# Schematic.net
KiCad netlist of a schematic drawn in Altium Designer
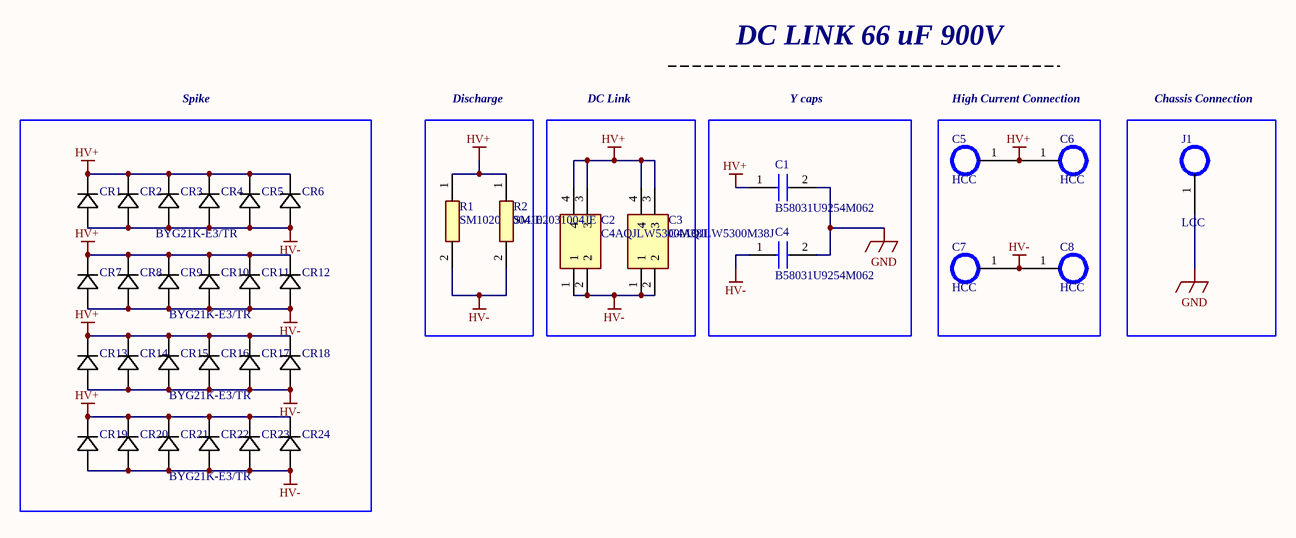
[diagram p0: Schematic.SchDoc]

(export (version "E")
  (design (tool "Eeschema 10.0.6"))
  (components
    (comp (ref "C1")
      (value "B58031U9254M062")
      (footprint "B58031U9254M062")
      (description "Capacitor")
      (fields (field (name "MOUSER PART NUMBER") "871-B58031U9254M062"))
      (libsource (lib "Schlib3") (part "B58031U9254M062"))
    )
    (comp (ref "C2")
      (value "C4AQJLW5300M38J")
      (footprint "PcbLib3:C4AQJLW5300M38J")
      (description "Capacitor")
      (fields (field (name "MOUSER PART NUMBER") "80-C4AQJLW5300M38J"))
      (libsource (lib "Schlib3") (part "C4AQJLW5300M38J"))
    )
    (comp (ref "C3")
      (value "C4AQJLW5300M38J")
      (footprint "PcbLib3:C4AQJLW5300M38J")
      (description "Capacitor")
      (fields (field (name "MOUSER PART NUMBER") "80-C4AQJLW5300M38J"))
      (libsource (lib "Schlib3") (part "C4AQJLW5300M38J"))
    )
    (comp (ref "C4")
      (value "B58031U9254M062")
      (footprint "B58031U9254M062")
      (description "Capacitor")
      (fields (field (name "MOUSER PART NUMBER") "871-B58031U9254M062"))
      (libsource (lib "Schlib3") (part "B58031U9254M062"))
    )
    (comp (ref "C5") (value "HCC") (footprint "6mm Pad") (libsource (lib "Schlib3") (part "HCC")))
    (comp (ref "C6") (value "HCC") (footprint "6mm Pad") (libsource (lib "Schlib3") (part "HCC")))
    (comp (ref "C7") (value "HCC") (footprint "6mm Pad") (libsource (lib "Schlib3") (part "HCC")))
    (comp (ref "C8") (value "HCC") (footprint "6mm Pad") (libsource (lib "Schlib3") (part "HCC")))
    (comp (ref "CR1")
      (value "BYG21K-E3/TR")
      (footprint "DO-214AC_VIS")
      (description "1.5A,800V,120nS FS AVALANCHE SMD")
      (fields (field (name "COPYRIGHT") "Copyright (C) 2025 Ultra Librarian. All rights reserved."))
      (libsource (lib "Schlib3") (part "BYG21K-E3TR"))
    )
    (comp (ref "CR2")
      (value "BYG21K-E3/TR")
      (footprint "DO-214AC_VIS")
      (description "1.5A,800V,120nS FS AVALANCHE SMD")
      (fields (field (name "COPYRIGHT") "Copyright (C) 2025 Ultra Librarian. All rights reserved."))
      (libsource (lib "Schlib3") (part "BYG21K-E3TR"))
    )
    (comp (ref "CR3")
      (value "BYG21K-E3/TR")
      (footprint "DO-214AC_VIS")
      (description "1.5A,800V,120nS FS AVALANCHE SMD")
      (fields (field (name "COPYRIGHT") "Copyright (C) 2025 Ultra Librarian. All rights reserved."))
      (libsource (lib "Schlib3") (part "BYG21K-E3TR"))
    )
    (comp (ref "CR4")
      (value "BYG21K-E3/TR")
      (footprint "DO-214AC_VIS")
      (description "1.5A,800V,120nS FS AVALANCHE SMD")
      (fields (field (name "COPYRIGHT") "Copyright (C) 2025 Ultra Librarian. All rights reserved."))
      (libsource (lib "Schlib3") (part "BYG21K-E3TR"))
    )
    (comp (ref "CR5")
      (value "BYG21K-E3/TR")
      (footprint "DO-214AC_VIS")
      (description "1.5A,800V,120nS FS AVALANCHE SMD")
      (fields (field (name "COPYRIGHT") "Copyright (C) 2025 Ultra Librarian. All rights reserved."))
      (libsource (lib "Schlib3") (part "BYG21K-E3TR"))
    )
    (comp (ref "CR6")
      (value "BYG21K-E3/TR")
      (footprint "DO-214AC_VIS")
      (description "1.5A,800V,120nS FS AVALANCHE SMD")
      (fields (field (name "COPYRIGHT") "Copyright (C) 2025 Ultra Librarian. All rights reserved."))
      (libsource (lib "Schlib3") (part "BYG21K-E3TR"))
    )
    (comp (ref "CR7")
      (value "BYG21K-E3/TR")
      (footprint "DO-214AC_VIS")
      (description "1.5A,800V,120nS FS AVALANCHE SMD")
      (fields (field (name "COPYRIGHT") "Copyright (C) 2025 Ultra Librarian. All rights reserved."))
      (libsource (lib "Schlib3") (part "BYG21K-E3TR"))
    )
    (comp (ref "CR8")
      (value "BYG21K-E3/TR")
      (footprint "DO-214AC_VIS")
      (description "1.5A,800V,120nS FS AVALANCHE SMD")
      (fields (field (name "COPYRIGHT") "Copyright (C) 2025 Ultra Librarian. All rights reserved."))
      (libsource (lib "Schlib3") (part "BYG21K-E3TR"))
    )
    (comp (ref "CR9")
      (value "BYG21K-E3/TR")
      (footprint "DO-214AC_VIS")
      (description "1.5A,800V,120nS FS AVALANCHE SMD")
      (fields (field (name "COPYRIGHT") "Copyright (C) 2025 Ultra Librarian. All rights reserved."))
      (libsource (lib "Schlib3") (part "BYG21K-E3TR"))
    )
    (comp (ref "CR10")
      (value "BYG21K-E3/TR")
      (footprint "DO-214AC_VIS")
      (description "1.5A,800V,120nS FS AVALANCHE SMD")
      (fields (field (name "COPYRIGHT") "Copyright (C) 2025 Ultra Librarian. All rights reserved."))
      (libsource (lib "Schlib3") (part "BYG21K-E3TR"))
    )
    (comp (ref "CR11")
      (value "BYG21K-E3/TR")
      (footprint "DO-214AC_VIS")
      (description "1.5A,800V,120nS FS AVALANCHE SMD")
      (fields (field (name "COPYRIGHT") "Copyright (C) 2025 Ultra Librarian. All rights reserved."))
      (libsource (lib "Schlib3") (part "BYG21K-E3TR"))
    )
    (comp (ref "CR12")
      (value "BYG21K-E3/TR")
      (footprint "DO-214AC_VIS")
      (description "1.5A,800V,120nS FS AVALANCHE SMD")
      (fields (field (name "COPYRIGHT") "Copyright (C) 2025 Ultra Librarian. All rights reserved."))
      (libsource (lib "Schlib3") (part "BYG21K-E3TR"))
    )
    (comp (ref "CR13")
      (value "BYG21K-E3/TR")
      (footprint "DO-214AC_VIS")
      (description "1.5A,800V,120nS FS AVALANCHE SMD")
      (fields (field (name "COPYRIGHT") "Copyright (C) 2025 Ultra Librarian. All rights reserved."))
      (libsource (lib "Schlib3") (part "BYG21K-E3TR"))
    )
    (comp (ref "CR14")
      (value "BYG21K-E3/TR")
      (footprint "DO-214AC_VIS")
      (description "1.5A,800V,120nS FS AVALANCHE SMD")
      (fields (field (name "COPYRIGHT") "Copyright (C) 2025 Ultra Librarian. All rights reserved."))
      (libsource (lib "Schlib3") (part "BYG21K-E3TR"))
    )
    (comp (ref "CR15")
      (value "BYG21K-E3/TR")
      (footprint "DO-214AC_VIS")
      (description "1.5A,800V,120nS FS AVALANCHE SMD")
      (fields (field (name "COPYRIGHT") "Copyright (C) 2025 Ultra Librarian. All rights reserved."))
      (libsource (lib "Schlib3") (part "BYG21K-E3TR"))
    )
    (comp (ref "CR16")
      (value "BYG21K-E3/TR")
      (footprint "DO-214AC_VIS")
      (description "1.5A,800V,120nS FS AVALANCHE SMD")
      (fields (field (name "COPYRIGHT") "Copyright (C) 2025 Ultra Librarian. All rights reserved."))
      (libsource (lib "Schlib3") (part "BYG21K-E3TR"))
    )
    (comp (ref "CR17")
      (value "BYG21K-E3/TR")
      (footprint "DO-214AC_VIS")
      (description "1.5A,800V,120nS FS AVALANCHE SMD")
      (fields (field (name "COPYRIGHT") "Copyright (C) 2025 Ultra Librarian. All rights reserved."))
      (libsource (lib "Schlib3") (part "BYG21K-E3TR"))
    )
    (comp (ref "CR18")
      (value "BYG21K-E3/TR")
      (footprint "DO-214AC_VIS")
      (description "1.5A,800V,120nS FS AVALANCHE SMD")
      (fields (field (name "COPYRIGHT") "Copyright (C) 2025 Ultra Librarian. All rights reserved."))
      (libsource (lib "Schlib3") (part "BYG21K-E3TR"))
    )
    (comp (ref "CR19")
      (value "BYG21K-E3/TR")
      (footprint "DO-214AC_VIS")
      (description "1.5A,800V,120nS FS AVALANCHE SMD")
      (fields (field (name "COPYRIGHT") "Copyright (C) 2025 Ultra Librarian. All rights reserved."))
      (libsource (lib "Schlib3") (part "BYG21K-E3TR"))
    )
    (comp (ref "CR20")
      (value "BYG21K-E3/TR")
      (footprint "DO-214AC_VIS")
      (description "1.5A,800V,120nS FS AVALANCHE SMD")
      (fields (field (name "COPYRIGHT") "Copyright (C) 2025 Ultra Librarian. All rights reserved."))
      (libsource (lib "Schlib3") (part "BYG21K-E3TR"))
    )
    (comp (ref "CR21")
      (value "BYG21K-E3/TR")
      (footprint "DO-214AC_VIS")
      (description "1.5A,800V,120nS FS AVALANCHE SMD")
      (fields (field (name "COPYRIGHT") "Copyright (C) 2025 Ultra Librarian. All rights reserved."))
      (libsource (lib "Schlib3") (part "BYG21K-E3TR"))
    )
    (comp (ref "CR22")
      (value "BYG21K-E3/TR")
      (footprint "DO-214AC_VIS")
      (description "1.5A,800V,120nS FS AVALANCHE SMD")
      (fields (field (name "COPYRIGHT") "Copyright (C) 2025 Ultra Librarian. All rights reserved."))
      (libsource (lib "Schlib3") (part "BYG21K-E3TR"))
    )
    (comp (ref "CR23")
      (value "BYG21K-E3/TR")
      (footprint "DO-214AC_VIS")
      (description "1.5A,800V,120nS FS AVALANCHE SMD")
      (fields (field (name "COPYRIGHT") "Copyright (C) 2025 Ultra Librarian. All rights reserved."))
      (libsource (lib "Schlib3") (part "BYG21K-E3TR"))
    )
    (comp (ref "CR24")
      (value "BYG21K-E3/TR")
      (footprint "DO-214AC_VIS")
      (description "1.5A,800V,120nS FS AVALANCHE SMD")
      (fields (field (name "COPYRIGHT") "Copyright (C) 2025 Ultra Librarian. All rights reserved."))
      (libsource (lib "Schlib3") (part "BYG21K-E3TR"))
    )
    (comp (ref "J1") (value "LCC") (footprint "PAD 3MM") (libsource (lib "Schlib3") (part "LCC")))
    (comp (ref "R1")
      (value "SM102031004JE")
      (footprint "PcbLib3:SM102031004JE")
      (description "Resistor")
      (libsource (lib "Schlib3") (part "SM102031004JE"))
    )
    (comp (ref "R2")
      (value "SM102031004JE")
      (footprint "PcbLib3:SM102031004JE")
      (description "Resistor")
      (libsource (lib "Schlib3") (part "SM102031004JE"))
    )
  )
  (nets
    (net (code "1") (name "GND") (class "Default")
      (node (ref "C1") (pin "2") (pinfunction "2_2") (pintype "passive"))
      (node (ref "C4") (pin "2") (pinfunction "2_2") (pintype "passive"))
      (node (ref "J1") (pin "1") (pintype "passive"))
    )
    (net (code "2") (name "HV+") (class "Default")
      (node (ref "C1") (pin "1") (pinfunction "1_1") (pintype "passive"))
      (node (ref "C2") (pin "3") (pinfunction "3_3") (pintype "passive"))
      (node (ref "C2") (pin "4") (pinfunction "4_4") (pintype "passive"))
      (node (ref "C3") (pin "3") (pinfunction "3_3") (pintype "passive"))
      (node (ref "C3") (pin "4") (pinfunction "4_4") (pintype "passive"))
      (node (ref "C5") (pin "1") (pintype "passive"))
      (node (ref "C6") (pin "1") (pintype "passive"))
      (node (ref "CR1") (pin "1") (pinfunction "1_1") (pintype "passive"))
      (node (ref "CR10") (pin "1") (pinfunction "1_1") (pintype "passive"))
      (node (ref "CR11") (pin "1") (pinfunction "1_1") (pintype "passive"))
      (node (ref "CR12") (pin "1") (pinfunction "1_1") (pintype "passive"))
      (node (ref "CR13") (pin "1") (pinfunction "1_1") (pintype "passive"))
      (node (ref "CR14") (pin "1") (pinfunction "1_1") (pintype "passive"))
      (node (ref "CR15") (pin "1") (pinfunction "1_1") (pintype "passive"))
      (node (ref "CR16") (pin "1") (pinfunction "1_1") (pintype "passive"))
      (node (ref "CR17") (pin "1") (pinfunction "1_1") (pintype "passive"))
      (node (ref "CR18") (pin "1") (pinfunction "1_1") (pintype "passive"))
      (node (ref "CR19") (pin "1") (pinfunction "1_1") (pintype "passive"))
      (node (ref "CR2") (pin "1") (pinfunction "1_1") (pintype "passive"))
      (node (ref "CR20") (pin "1") (pinfunction "1_1") (pintype "passive"))
      (node (ref "CR21") (pin "1") (pinfunction "1_1") (pintype "passive"))
      (node (ref "CR22") (pin "1") (pinfunction "1_1") (pintype "passive"))
      (node (ref "CR23") (pin "1") (pinfunction "1_1") (pintype "passive"))
      (node (ref "CR24") (pin "1") (pinfunction "1_1") (pintype "passive"))
      (node (ref "CR3") (pin "1") (pinfunction "1_1") (pintype "passive"))
      (node (ref "CR4") (pin "1") (pinfunction "1_1") (pintype "passive"))
      (node (ref "CR5") (pin "1") (pinfunction "1_1") (pintype "passive"))
      (node (ref "CR6") (pin "1") (pinfunction "1_1") (pintype "passive"))
      (node (ref "CR7") (pin "1") (pinfunction "1_1") (pintype "passive"))
      (node (ref "CR8") (pin "1") (pinfunction "1_1") (pintype "passive"))
      (node (ref "CR9") (pin "1") (pinfunction "1_1") (pintype "passive"))
      (node (ref "R1") (pin "1") (pinfunction "1_1") (pintype "passive"))
      (node (ref "R2") (pin "1") (pinfunction "1_1") (pintype "passive"))
    )
    (net (code "3") (name "HV-") (class "Default")
      (node (ref "C2") (pin "1") (pinfunction "1_1") (pintype "passive"))
      (node (ref "C2") (pin "2") (pinfunction "2_2") (pintype "passive"))
      (node (ref "C3") (pin "1") (pinfunction "1_1") (pintype "passive"))
      (node (ref "C3") (pin "2") (pinfunction "2_2") (pintype "passive"))
      (node (ref "C4") (pin "1") (pinfunction "1_1") (pintype "passive"))
      (node (ref "C7") (pin "1") (pintype "passive"))
      (node (ref "C8") (pin "1") (pintype "passive"))
      (node (ref "CR1") (pin "2") (pinfunction "2_2") (pintype "passive"))
      (node (ref "CR10") (pin "2") (pinfunction "2_2") (pintype "passive"))
      (node (ref "CR11") (pin "2") (pinfunction "2_2") (pintype "passive"))
      (node (ref "CR12") (pin "2") (pinfunction "2_2") (pintype "passive"))
      (node (ref "CR13") (pin "2") (pinfunction "2_2") (pintype "passive"))
      (node (ref "CR14") (pin "2") (pinfunction "2_2") (pintype "passive"))
      (node (ref "CR15") (pin "2") (pinfunction "2_2") (pintype "passive"))
      (node (ref "CR16") (pin "2") (pinfunction "2_2") (pintype "passive"))
      (node (ref "CR17") (pin "2") (pinfunction "2_2") (pintype "passive"))
      (node (ref "CR18") (pin "2") (pinfunction "2_2") (pintype "passive"))
      (node (ref "CR19") (pin "2") (pinfunction "2_2") (pintype "passive"))
      (node (ref "CR2") (pin "2") (pinfunction "2_2") (pintype "passive"))
      (node (ref "CR20") (pin "2") (pinfunction "2_2") (pintype "passive"))
      (node (ref "CR21") (pin "2") (pinfunction "2_2") (pintype "passive"))
      (node (ref "CR22") (pin "2") (pinfunction "2_2") (pintype "passive"))
      (node (ref "CR23") (pin "2") (pinfunction "2_2") (pintype "passive"))
      (node (ref "CR24") (pin "2") (pinfunction "2_2") (pintype "passive"))
      (node (ref "CR3") (pin "2") (pinfunction "2_2") (pintype "passive"))
      (node (ref "CR4") (pin "2") (pinfunction "2_2") (pintype "passive"))
      (node (ref "CR5") (pin "2") (pinfunction "2_2") (pintype "passive"))
      (node (ref "CR6") (pin "2") (pinfunction "2_2") (pintype "passive"))
      (node (ref "CR7") (pin "2") (pinfunction "2_2") (pintype "passive"))
      (node (ref "CR8") (pin "2") (pinfunction "2_2") (pintype "passive"))
      (node (ref "CR9") (pin "2") (pinfunction "2_2") (pintype "passive"))
      (node (ref "R1") (pin "2") (pinfunction "2_2") (pintype "passive"))
      (node (ref "R2") (pin "2") (pinfunction "2_2") (pintype "passive"))
    )
  )
)
